# untitled.net
KiCad netlist of a schematic drawn in EAGLE
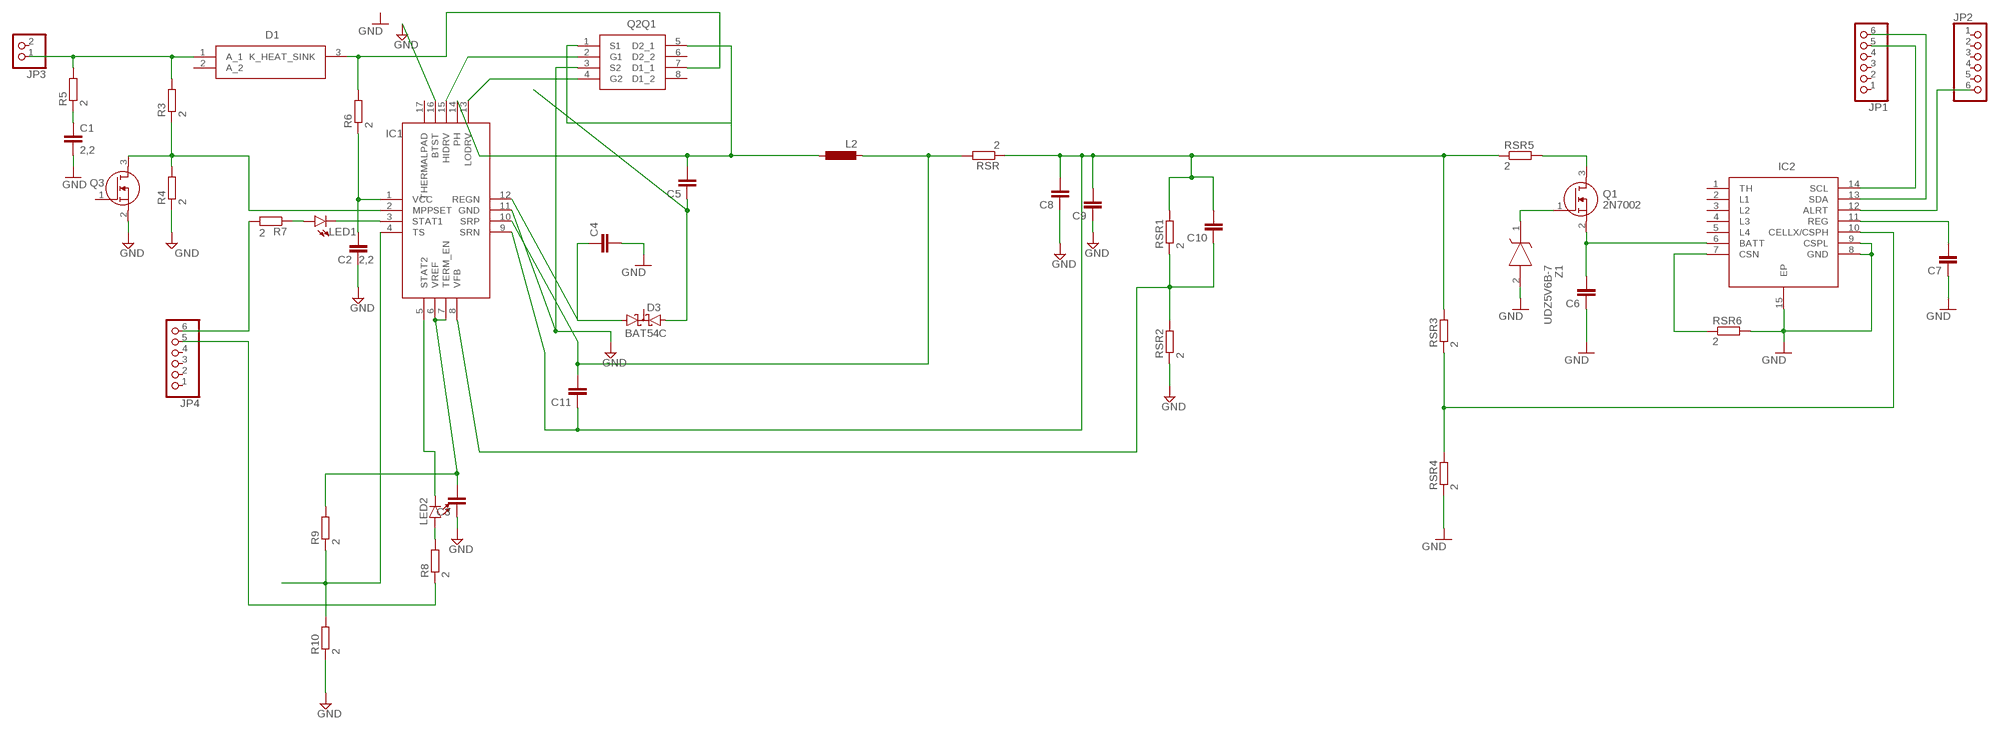
[diagram p0: schematic, sheet 1]

(export (version "E")
  (design (tool "Eeschema 10.0.6"))
  (components
    (comp (ref "C1")
      (value "2,2")
      (footprint "eagle-import:C0805K")
      (libsource (lib "eagle-import") (part "C-EUC0805K"))
    )
    (comp (ref "C2")
      (value "2,2")
      (footprint "eagle-import:C0805K")
      (libsource (lib "eagle-import") (part "C-EUC0805K"))
    )
    (comp (ref "C3")
      (value "2,2")
      (footprint "eagle-import:C0805K")
      (libsource (lib "eagle-import") (part "C-EUC0805K"))
    )
    (comp (ref "C4")
      (value "2,2")
      (footprint "eagle-import:C0805K")
      (libsource (lib "eagle-import") (part "C-EUC0805K"))
    )
    (comp (ref "C5")
      (value "2,2")
      (footprint "eagle-import:C0805K")
      (libsource (lib "eagle-import") (part "C-EUC0805K"))
    )
    (comp (ref "C6")
      (value "2,2")
      (footprint "eagle-import:C0805K")
      (libsource (lib "eagle-import") (part "C-EUC0805K"))
    )
    (comp (ref "C7")
      (value "2,2")
      (footprint "eagle-import:C0805K")
      (libsource (lib "eagle-import") (part "C-EUC0805K"))
    )
    (comp (ref "C8")
      (value "2,2")
      (footprint "eagle-import:C0805K")
      (libsource (lib "eagle-import") (part "C-EUC0805K"))
    )
    (comp (ref "C9")
      (value "2,2")
      (footprint "eagle-import:C0805K")
      (libsource (lib "eagle-import") (part "C-EUC0805K"))
    )
    (comp (ref "C10")
      (value "2,2")
      (footprint "eagle-import:C0805K")
      (libsource (lib "eagle-import") (part "C-EUC0805K"))
    )
    (comp (ref "C11")
      (value "2,2")
      (footprint "eagle-import:C0805K")
      (libsource (lib "eagle-import") (part "C-EUC0805K"))
    )
    (comp (ref "D1")
      (value "PDS1040Q-13")
      (footprint "eagle-import:PDS104013")
      (fields (field (name "MOUSER_PART_NUMBER") "621-PDS1040Q-13"))
      (libsource (lib "eagle-import") (part "PDS1040Q-13"))
    )
    (comp (ref "D3")
      (value "BAT54C")
      (footprint "eagle-import:SOT23")
      (libsource (lib "eagle-import") (part "BAT54C"))
    )
    (comp (ref "IC1")
      (value "BQ24650RVAT")
      (footprint "eagle-import:QFN50P350X350X100-17N")
      (fields (field (name "MOUSER_PART_NUMBER") "595-BQ24650RVAT"))
      (libsource (lib "eagle-import") (part "BQ24650RVAT"))
    )
    (comp (ref "IC2")
      (value "MAX17263LETD+")
      (footprint "eagle-import:SON40P300X300X80-15N")
      (fields (field (name "MOUSER_PART_NUMBER") "700-MAX17263LETD+"))
      (libsource (lib "eagle-import") (part "MAX17263LETD+"))
    )
    (comp (ref "JP1")
      (value "PINHD-1X6")
      (footprint "eagle-import:1X06")
      (libsource (lib "eagle-import") (part "PINHD-1X6"))
    )
    (comp (ref "JP2")
      (value "PINHD-1X6")
      (footprint "eagle-import:1X06")
      (libsource (lib "eagle-import") (part "PINHD-1X6"))
    )
    (comp (ref "JP3")
      (value "PINHD-1X2")
      (footprint "eagle-import:1X02")
      (libsource (lib "eagle-import") (part "PINHD-1X2"))
    )
    (comp (ref "JP4")
      (value "PINHD-1X6")
      (footprint "eagle-import:1X06")
      (libsource (lib "eagle-import") (part "PINHD-1X6"))
    )
    (comp (ref "L2")
      (value "L-EUL2825P")
      (footprint "eagle-import:L2825P")
      (libsource (lib "eagle-import") (part "L-EUL2825P"))
    )
    (comp (ref "LED1")
      (value "LAP4-BOTTOM")
      (footprint "eagle-import:P47F-BOTTOM")
      (libsource (lib "eagle-import") (part "P4-BOTTOMLA"))
    )
    (comp (ref "LED2")
      (value "LAP4-BOTTOM")
      (footprint "eagle-import:P47F-BOTTOM")
      (libsource (lib "eagle-import") (part "P4-BOTTOMLA"))
    )
    (comp (ref "Q1")
      (value "2N7002")
      (footprint "eagle-import:SOT96P240X120-3N")
      (fields (field (name "MOUSER_PART_NUMBER") "512-2N7002"))
      (libsource (lib "eagle-import") (part "2N7002"))
    )
    (comp (ref "Q2Q1")
      (value "SI7288DP-T1-GE3")
      (footprint "eagle-import:POWERPAK-SO8_1")
      (fields (field (name "MOUSER_PART_NUMBER") "781-SI7288DP-T1-GE3"))
      (libsource (lib "eagle-import") (part "SI7288DP-T1-GE3"))
    )
    (comp (ref "Q3")
      (value "2N7002")
      (footprint "eagle-import:SOT96P240X120-3N")
      (fields (field (name "MOUSER_PART_NUMBER") "512-2N7002"))
      (libsource (lib "eagle-import") (part "2N7002"))
    )
    (comp (ref "R3")
      (value "2")
      (footprint "eagle-import:M1206")
      (libsource (lib "eagle-import") (part "R-EU_M1206"))
    )
    (comp (ref "R4")
      (value "2")
      (footprint "eagle-import:M1206")
      (libsource (lib "eagle-import") (part "R-EU_M1206"))
    )
    (comp (ref "R5")
      (value "2")
      (footprint "eagle-import:M1206")
      (libsource (lib "eagle-import") (part "R-EU_M1206"))
    )
    (comp (ref "R6")
      (value "2")
      (footprint "eagle-import:M1206")
      (libsource (lib "eagle-import") (part "R-EU_M1206"))
    )
    (comp (ref "R7")
      (value "2")
      (footprint "eagle-import:M1206")
      (libsource (lib "eagle-import") (part "R-EU_M1206"))
    )
    (comp (ref "R8")
      (value "2")
      (footprint "eagle-import:M1206")
      (libsource (lib "eagle-import") (part "R-EU_M1206"))
    )
    (comp (ref "R9")
      (value "2")
      (footprint "eagle-import:M1206")
      (libsource (lib "eagle-import") (part "R-EU_M1206"))
    )
    (comp (ref "R10")
      (value "2")
      (footprint "eagle-import:M1206")
      (libsource (lib "eagle-import") (part "R-EU_M1206"))
    )
    (comp (ref "RSR")
      (value "2")
      (footprint "eagle-import:M1206")
      (libsource (lib "eagle-import") (part "R-EU_M1206"))
    )
    (comp (ref "RSR1")
      (value "2")
      (footprint "eagle-import:M1206")
      (libsource (lib "eagle-import") (part "R-EU_M1206"))
    )
    (comp (ref "RSR2")
      (value "2")
      (footprint "eagle-import:M1206")
      (libsource (lib "eagle-import") (part "R-EU_M1206"))
    )
    (comp (ref "RSR3")
      (value "2")
      (footprint "eagle-import:M1206")
      (libsource (lib "eagle-import") (part "R-EU_M1206"))
    )
    (comp (ref "RSR4")
      (value "2")
      (footprint "eagle-import:M1206")
      (libsource (lib "eagle-import") (part "R-EU_M1206"))
    )
    (comp (ref "RSR5")
      (value "2")
      (footprint "eagle-import:M1206")
      (libsource (lib "eagle-import") (part "R-EU_M1206"))
    )
    (comp (ref "RSR6")
      (value "2")
      (footprint "eagle-import:M1206")
      (libsource (lib "eagle-import") (part "R-EU_M1206"))
    )
    (comp (ref "Z1")
      (value "UDZ5V6B-7")
      (footprint "eagle-import:SOD2513X120N")
      (fields (field (name "MOUSER_PART_NUMBER") "621-UDZ5V6B-7"))
      (libsource (lib "eagle-import") (part "UDZ5V6B-7"))
    )
  )
  (nets
    (net (code "1") (name "GND") (class "Default")
      (node (ref "C1") (pin "2") (pinfunction "2_2") (pintype "passive"))
      (node (ref "C2") (pin "1") (pinfunction "1_1") (pintype "passive"))
      (node (ref "C3") (pin "1") (pinfunction "1_1") (pintype "passive"))
      (node (ref "C4") (pin "2") (pinfunction "2_2") (pintype "passive"))
      (node (ref "C6") (pin "1") (pinfunction "1_1") (pintype "passive"))
      (node (ref "C7") (pin "1") (pinfunction "1_1") (pintype "passive"))
      (node (ref "C8") (pin "1") (pinfunction "1_1") (pintype "passive"))
      (node (ref "C9") (pin "1") (pinfunction "1_1") (pintype "passive"))
      (node (ref "IC1") (pin "11") (pinfunction "GND_11") (pintype "bidirectional"))
      (node (ref "IC1") (pin "16") (pinfunction "BTST_16") (pintype "bidirectional"))
      (node (ref "IC2") (pin "15") (pinfunction "EP_15") (pintype "bidirectional"))
      (node (ref "IC2") (pin "8") (pinfunction "GND_8") (pintype "bidirectional"))
      (node (ref "IC2") (pin "9") (pinfunction "CSPL_9") (pintype "bidirectional"))
      (node (ref "Q2Q1") (pin "3") (pinfunction "S2_3") (pintype "bidirectional"))
      (node (ref "Q3") (pin "2") (pinfunction "S_2") (pintype "bidirectional"))
      (node (ref "R10") (pin "1") (pinfunction "1_1") (pintype "passive"))
      (node (ref "R4") (pin "1") (pinfunction "1_1") (pintype "passive"))
      (node (ref "RSR2") (pin "1") (pinfunction "1_1") (pintype "passive"))
      (node (ref "RSR4") (pin "1") (pinfunction "1_1") (pintype "passive"))
      (node (ref "RSR6") (pin "2") (pinfunction "2_2") (pintype "passive"))
      (node (ref "Z1") (pin "2") (pinfunction "A_2") (pintype "bidirectional"))
    )
    (net (code "2") (name "Net-(C1-Pad1)") (class "Default")
      (node (ref "C1") (pin "1") (pinfunction "1_1") (pintype "passive"))
      (node (ref "R5") (pin "1") (pinfunction "1_1") (pintype "passive"))
    )
    (net (code "3") (name "Net-(D1-A_1)") (class "Default")
      (node (ref "D1") (pin "1") (pinfunction "A_1_1") (pintype "bidirectional"))
      (node (ref "JP3") (pin "1") (pinfunction "1_1") (pintype "passive"))
      (node (ref "R3") (pin "2") (pinfunction "2_2") (pintype "passive"))
      (node (ref "R5") (pin "2") (pinfunction "2_2") (pintype "passive"))
    )
    (net (code "4") (name "Net-(D1-K_HEAT_SINK)") (class "Default")
      (node (ref "D1") (pin "3") (pinfunction "K_HEAT_SINK_3") (pintype "bidirectional"))
      (node (ref "Q2Q1") (pin "7") (pinfunction "D1_1_7") (pintype "bidirectional"))
      (node (ref "R6") (pin "2") (pinfunction "2_2") (pintype "passive"))
    )
    (net (code "5") (name "Net-(D3-A1)") (class "Default")
      (node (ref "C4") (pin "1") (pinfunction "1_1") (pintype "passive"))
      (node (ref "D3") (pin "1") (pinfunction "A1_1") (pintype "passive"))
      (node (ref "IC1") (pin "12") (pinfunction "REGN_12") (pintype "bidirectional"))
    )
    (net (code "6") (name "Net-(D3-A2)") (class "Default")
      (node (ref "C5") (pin "1") (pinfunction "1_1") (pintype "passive"))
      (node (ref "D3") (pin "2") (pinfunction "A2_2") (pintype "passive"))
    )
    (net (code "7") (name "Net-(IC1-HIDRV)") (class "Default")
      (node (ref "IC1") (pin "15") (pinfunction "HIDRV_15") (pintype "bidirectional"))
      (node (ref "Q2Q1") (pin "2") (pinfunction "G1_2") (pintype "bidirectional"))
    )
    (net (code "8") (name "Net-(IC1-LODRV)") (class "Default")
      (node (ref "IC1") (pin "13") (pinfunction "LODRV_13") (pintype "bidirectional"))
      (node (ref "Q2Q1") (pin "4") (pinfunction "G2_4") (pintype "bidirectional"))
    )
    (net (code "9") (name "Net-(IC1-MPPSET)") (class "Default")
      (node (ref "IC1") (pin "2") (pinfunction "MPPSET_2") (pintype "bidirectional"))
      (node (ref "Q3") (pin "3") (pinfunction "D_3") (pintype "bidirectional"))
      (node (ref "R3") (pin "1") (pinfunction "1_1") (pintype "passive"))
      (node (ref "R4") (pin "2") (pinfunction "2_2") (pintype "passive"))
    )
    (net (code "10") (name "Net-(IC1-PH)") (class "Default")
      (node (ref "C5") (pin "2") (pinfunction "2_2") (pintype "passive"))
      (node (ref "IC1") (pin "14") (pinfunction "PH_14") (pintype "bidirectional"))
      (node (ref "L2") (pin "1") (pinfunction "1_1") (pintype "passive"))
      (node (ref "Q2Q1") (pin "1") (pinfunction "S1_1") (pintype "bidirectional"))
      (node (ref "Q2Q1") (pin "5") (pinfunction "D2_1_5") (pintype "bidirectional"))
    )
    (net (code "11") (name "Net-(IC1-SRN)") (class "Default")
      (node (ref "C10") (pin "2") (pinfunction "2_2") (pintype "passive"))
      (node (ref "C11") (pin "1") (pinfunction "1_1") (pintype "passive"))
      (node (ref "C8") (pin "2") (pinfunction "2_2") (pintype "passive"))
      (node (ref "C9") (pin "2") (pinfunction "2_2") (pintype "passive"))
      (node (ref "IC1") (pin "9") (pinfunction "SRN_9") (pintype "bidirectional"))
      (node (ref "RSR") (pin "1") (pinfunction "1_1") (pintype "passive"))
      (node (ref "RSR1") (pin "2") (pinfunction "2_2") (pintype "passive"))
      (node (ref "RSR3") (pin "2") (pinfunction "2_2") (pintype "passive"))
      (node (ref "RSR5") (pin "1") (pinfunction "1_1") (pintype "passive"))
    )
    (net (code "12") (name "Net-(IC1-SRP)") (class "Default")
      (node (ref "C11") (pin "2") (pinfunction "2_2") (pintype "passive"))
      (node (ref "IC1") (pin "10") (pinfunction "SRP_10") (pintype "bidirectional"))
      (node (ref "L2") (pin "2") (pinfunction "2_2") (pintype "passive"))
      (node (ref "RSR") (pin "2") (pinfunction "2_2") (pintype "passive"))
    )
    (net (code "13") (name "Net-(IC1-STAT1)") (class "Default")
      (node (ref "IC1") (pin "3") (pinfunction "STAT1_3") (pintype "bidirectional"))
      (node (ref "LED1") (pin "C") (pinfunction "C_C") (pintype "passive"))
    )
    (net (code "14") (name "Net-(IC1-STAT2)") (class "Default")
      (node (ref "IC1") (pin "5") (pinfunction "STAT2_5") (pintype "bidirectional"))
      (node (ref "LED2") (pin "C") (pinfunction "C_C") (pintype "passive"))
    )
    (net (code "15") (name "Net-(IC1-TERM_EN)") (class "Default")
      (node (ref "C3") (pin "2") (pinfunction "2_2") (pintype "passive"))
      (node (ref "IC1") (pin "6") (pinfunction "VREF_6") (pintype "bidirectional"))
      (node (ref "IC1") (pin "7") (pinfunction "TERM_EN_7") (pintype "bidirectional"))
      (node (ref "R9") (pin "2") (pinfunction "2_2") (pintype "passive"))
    )
    (net (code "16") (name "Net-(IC1-TS)") (class "Default")
      (node (ref "IC1") (pin "4") (pinfunction "TS_4") (pintype "bidirectional"))
      (node (ref "R10") (pin "2") (pinfunction "2_2") (pintype "passive"))
      (node (ref "R9") (pin "1") (pinfunction "1_1") (pintype "passive"))
    )
    (net (code "17") (name "Net-(IC1-VCC)") (class "Default")
      (node (ref "C2") (pin "2") (pinfunction "2_2") (pintype "passive"))
      (node (ref "IC1") (pin "1") (pinfunction "VCC_1") (pintype "bidirectional"))
      (node (ref "R6") (pin "1") (pinfunction "1_1") (pintype "passive"))
    )
    (net (code "18") (name "Net-(IC1-VFB)") (class "Default")
      (node (ref "C10") (pin "1") (pinfunction "1_1") (pintype "passive"))
      (node (ref "IC1") (pin "8") (pinfunction "VFB_8") (pintype "bidirectional"))
      (node (ref "RSR1") (pin "1") (pinfunction "1_1") (pintype "passive"))
      (node (ref "RSR2") (pin "2") (pinfunction "2_2") (pintype "passive"))
    )
    (net (code "19") (name "Net-(IC2-ALRT)") (class "Default")
      (node (ref "IC2") (pin "12") (pinfunction "ALRT_12") (pintype "bidirectional"))
      (node (ref "JP2") (pin "6") (pinfunction "6_6") (pintype "passive"))
    )
    (net (code "20") (name "Net-(IC2-BATT)") (class "Default")
      (node (ref "C6") (pin "2") (pinfunction "2_2") (pintype "passive"))
      (node (ref "IC2") (pin "6") (pinfunction "BATT_6") (pintype "bidirectional"))
      (node (ref "Q1") (pin "2") (pinfunction "S_2") (pintype "bidirectional"))
    )
    (net (code "21") (name "Net-(IC2-CELLX{slash}CSPH)") (class "Default")
      (node (ref "IC2") (pin "10") (pinfunction "CELLX/CSPH_10") (pintype "bidirectional"))
      (node (ref "RSR3") (pin "1") (pinfunction "1_1") (pintype "passive"))
      (node (ref "RSR4") (pin "2") (pinfunction "2_2") (pintype "passive"))
    )
    (net (code "22") (name "Net-(IC2-CSN)") (class "Default")
      (node (ref "IC2") (pin "7") (pinfunction "CSN_7") (pintype "bidirectional"))
      (node (ref "RSR6") (pin "1") (pinfunction "1_1") (pintype "passive"))
    )
    (net (code "23") (name "Net-(IC2-REG)") (class "Default")
      (node (ref "C7") (pin "2") (pinfunction "2_2") (pintype "passive"))
      (node (ref "IC2") (pin "11") (pinfunction "REG_11") (pintype "bidirectional"))
    )
    (net (code "24") (name "Net-(IC2-SCL)") (class "Default")
      (node (ref "IC2") (pin "14") (pinfunction "SCL_14") (pintype "bidirectional"))
      (node (ref "JP1") (pin "5") (pinfunction "5_5") (pintype "passive"))
    )
    (net (code "25") (name "Net-(IC2-SDA)") (class "Default")
      (node (ref "IC2") (pin "13") (pinfunction "SDA_13") (pintype "bidirectional"))
      (node (ref "JP1") (pin "6") (pinfunction "6_6") (pintype "passive"))
    )
    (net (code "26") (name "Net-(JP4-Pad5)") (class "Default")
      (node (ref "JP4") (pin "5") (pinfunction "5_5") (pintype "passive"))
      (node (ref "R8") (pin "1") (pinfunction "1_1") (pintype "passive"))
    )
    (net (code "27") (name "Net-(JP4-Pad6)") (class "Default")
      (node (ref "JP4") (pin "6") (pinfunction "6_6") (pintype "passive"))
      (node (ref "R7") (pin "2") (pinfunction "2_2") (pintype "passive"))
    )
    (net (code "28") (name "Net-(LED1-PadA)") (class "Default")
      (node (ref "LED1") (pin "A") (pinfunction "A_A") (pintype "passive"))
      (node (ref "R7") (pin "1") (pinfunction "1_1") (pintype "passive"))
    )
    (net (code "29") (name "Net-(LED2-PadA)") (class "Default")
      (node (ref "LED2") (pin "A") (pinfunction "A_A") (pintype "passive"))
      (node (ref "R8") (pin "2") (pinfunction "2_2") (pintype "passive"))
    )
    (net (code "30") (name "Net-(Q1-D)") (class "Default")
      (node (ref "Q1") (pin "3") (pinfunction "D_3") (pintype "bidirectional"))
      (node (ref "RSR5") (pin "2") (pinfunction "2_2") (pintype "passive"))
    )
    (net (code "31") (name "Net-(Q1-G)") (class "Default")
      (node (ref "Q1") (pin "1") (pinfunction "G_1") (pintype "bidirectional"))
      (node (ref "Z1") (pin "1") (pinfunction "K_1") (pintype "bidirectional"))
    )
    (net (code "32") (name "unconnected-(D1-A_2-Pad2)") (class "Default")
      (node (ref "D1") (pin "2") (pinfunction "A_2_2") (pintype "bidirectional"))
    )
    (net (code "33") (name "unconnected-(D3-CC-Pad3)") (class "Default")
      (node (ref "D3") (pin "3") (pinfunction "CC_3") (pintype "passive"))
    )
    (net (code "34") (name "unconnected-(IC1-THERMALPAD-Pad17)") (class "Default")
      (node (ref "IC1") (pin "17") (pinfunction "THERMALPAD_17") (pintype "bidirectional"))
    )
    (net (code "35") (name "unconnected-(IC2-L1-Pad2)") (class "Default")
      (node (ref "IC2") (pin "2") (pinfunction "L1_2") (pintype "bidirectional"))
    )
    (net (code "36") (name "unconnected-(IC2-L2-Pad3)") (class "Default")
      (node (ref "IC2") (pin "3") (pinfunction "L2_3") (pintype "bidirectional"))
    )
    (net (code "37") (name "unconnected-(IC2-L3-Pad4)") (class "Default")
      (node (ref "IC2") (pin "4") (pinfunction "L3_4") (pintype "bidirectional"))
    )
    (net (code "38") (name "unconnected-(IC2-L4-Pad5)") (class "Default")
      (node (ref "IC2") (pin "5") (pinfunction "L4_5") (pintype "bidirectional"))
    )
    (net (code "39") (name "unconnected-(IC2-TH-Pad1)") (class "Default")
      (node (ref "IC2") (pin "1") (pinfunction "TH_1") (pintype "bidirectional"))
    )
    (net (code "40") (name "unconnected-(JP1-Pad1)") (class "Default")
      (node (ref "JP1") (pin "1") (pinfunction "1_1") (pintype "passive"))
    )
    (net (code "41") (name "unconnected-(JP1-Pad2)") (class "Default")
      (node (ref "JP1") (pin "2") (pinfunction "2_2") (pintype "passive"))
    )
    (net (code "42") (name "unconnected-(JP1-Pad3)") (class "Default")
      (node (ref "JP1") (pin "3") (pinfunction "3_3") (pintype "passive"))
    )
    (net (code "43") (name "unconnected-(JP1-Pad4)") (class "Default")
      (node (ref "JP1") (pin "4") (pinfunction "4_4") (pintype "passive"))
    )
    (net (code "44") (name "unconnected-(JP2-Pad1)") (class "Default")
      (node (ref "JP2") (pin "1") (pinfunction "1_1") (pintype "passive"))
    )
    (net (code "45") (name "unconnected-(JP2-Pad2)") (class "Default")
      (node (ref "JP2") (pin "2") (pinfunction "2_2") (pintype "passive"))
    )
    (net (code "46") (name "unconnected-(JP2-Pad3)") (class "Default")
      (node (ref "JP2") (pin "3") (pinfunction "3_3") (pintype "passive"))
    )
    (net (code "47") (name "unconnected-(JP2-Pad4)") (class "Default")
      (node (ref "JP2") (pin "4") (pinfunction "4_4") (pintype "passive"))
    )
    (net (code "48") (name "unconnected-(JP2-Pad5)") (class "Default")
      (node (ref "JP2") (pin "5") (pinfunction "5_5") (pintype "passive"))
    )
    (net (code "49") (name "unconnected-(JP3-Pad2)") (class "Default")
      (node (ref "JP3") (pin "2") (pinfunction "2_2") (pintype "passive"))
    )
    (net (code "50") (name "unconnected-(JP4-Pad1)") (class "Default")
      (node (ref "JP4") (pin "1") (pinfunction "1_1") (pintype "passive"))
    )
    (net (code "51") (name "unconnected-(JP4-Pad2)") (class "Default")
      (node (ref "JP4") (pin "2") (pinfunction "2_2") (pintype "passive"))
    )
    (net (code "52") (name "unconnected-(JP4-Pad3)") (class "Default")
      (node (ref "JP4") (pin "3") (pinfunction "3_3") (pintype "passive"))
    )
    (net (code "53") (name "unconnected-(JP4-Pad4)") (class "Default")
      (node (ref "JP4") (pin "4") (pinfunction "4_4") (pintype "passive"))
    )
    (net (code "54") (name "unconnected-(Q2Q1-D1_2-Pad8)") (class "Default")
      (node (ref "Q2Q1") (pin "8") (pinfunction "D1_2_8") (pintype "bidirectional"))
    )
    (net (code "55") (name "unconnected-(Q2Q1-D2_2-Pad6)") (class "Default")
      (node (ref "Q2Q1") (pin "6") (pinfunction "D2_2_6") (pintype "bidirectional"))
    )
    (net (code "56") (name "unconnected-(Q3-G-Pad1)") (class "Default")
      (node (ref "Q3") (pin "1") (pinfunction "G_1") (pintype "bidirectional"))
    )
  )
)
